# ARM_EURO_Platine2.net
KiCad netlist of a schematic drawn in Altium Designer
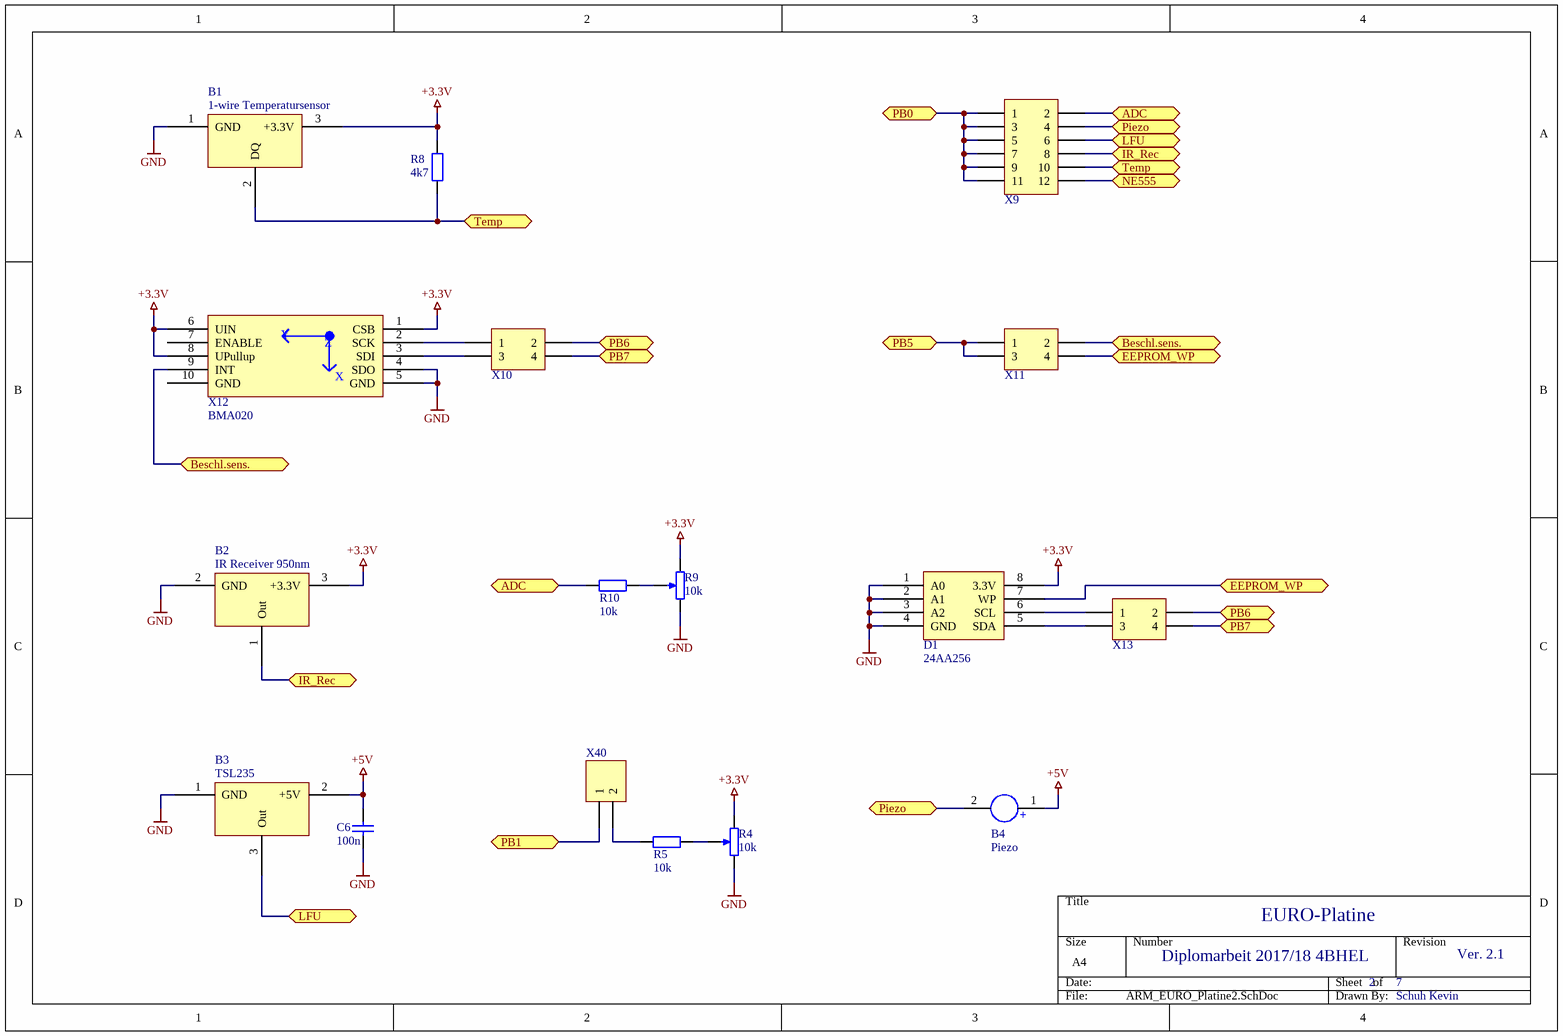
[diagram p0: ARM_EURO_Platine2.SchDoc]

(export (version "E")
  (design (tool "Eeschema 10.0.6"))
  (components
    (comp (ref "B1")
      (value "1-wire Temperatursensor")
      (footprint "TO_92")
      (description "Temperatursensor")
      (libsource (lib "ARM_Libary_EURO") (part "DS18B20"))
    )
    (comp (ref "B2")
      (value "IR Receiver 950nm")
      (footprint "TSOP341")
      (description "IR-Empfänger")
      (libsource (lib "ARM_Libary_EURO") (part "IR_Receiver"))
    )
    (comp (ref "B3")
      (value "TSL235")
      (footprint "LFU")
      (description "Licht/Frequenz - Umwandler")
      (libsource (lib "ARM_Libary_EURO") (part "LFU"))
    )
    (comp (ref "B4")
      (value "Piezo")
      (footprint "Piezo")
      (description "Signalgeber")
      (libsource (lib "ARM_Libary_EURO") (part "Piezo"))
    )
    (comp (ref "C6")
      (value "100n")
      (footprint "0805_CAP")
      (description "Capacitor_SMD")
      (fields (field (name "Comment") "Cap_Keramik_SMD") (field (name "PUBLISHER") "Altium Limited"))
      (libsource (lib "ARM_Libary_EURO") (part "Cap_Keramik_SMD"))
    )
    (comp (ref "D1")
      (value "24AA256")
      (footprint "PDIP8")
      (description "32kx8 EEPROM")
      (libsource (lib "ARM_Libary_EURO") (part "EEPROM"))
    )
    (comp (ref "R4")
      (value "10k")
      (footprint "Potentiometer")
      (description "Potentiometer")
      (fields (field (name "Comment") "RPot") (field (name "PUBLISHER") "Altium Limited"))
      (libsource (lib "ARM_Libary_EURO") (part "RPot"))
    )
    (comp (ref "R5")
      (value "10k")
      (footprint "0805_Res")
      (description "Resistor")
      (fields (field (name "Comment") "Res_SMD") (field (name "PUBLISHER") "Altium Limited"))
      (libsource (lib "ARM_Libary_EURO") (part "Res_SMD"))
    )
    (comp (ref "R8")
      (value "4k7")
      (footprint "0805_Res")
      (description "Resistor")
      (fields (field (name "Comment") "Res_SMD") (field (name "PUBLISHER") "Altium Limited"))
      (libsource (lib "") (part "Res_SMD_1"))
    )
    (comp (ref "R9")
      (value "10k")
      (footprint "Potentiometer")
      (description "Potentiometer")
      (fields (field (name "Comment") "RPot") (field (name "PUBLISHER") "Altium Limited"))
      (libsource (lib "ARM_Libary_EURO") (part "RPot"))
    )
    (comp (ref "R10")
      (value "10k")
      (footprint "0805_Res")
      (description "Resistor")
      (fields (field (name "Comment") "Res_SMD") (field (name "PUBLISHER") "Altium Limited"))
      (libsource (lib "ARM_Libary_EURO") (part "Res_SMD"))
    )
    (comp (ref "X9")
      (value "Header 6X2A")
      (footprint "HDR2X6")
      (description "Header, 6-Pin, Dual row")
      (fields (field (name "PUBLISHER") "Altium Limited"))
      (libsource (lib "ARM_Libary_EURO") (part "Header_6X2A"))
    )
    (comp (ref "X10")
      (value "Header_2x2")
      (footprint "HDR2X2")
      (description "Header, 3x2-Pin")
      (fields (field (name "PUBLISHER") "Altium Limited"))
      (libsource (lib "ARM_Libary_EURO") (part "Header_2x2"))
    )
    (comp (ref "X11")
      (value "Header_2x2")
      (footprint "HDR2X2")
      (description "Header, 3x2-Pin")
      (fields (field (name "PUBLISHER") "Altium Limited"))
      (libsource (lib "ARM_Libary_EURO") (part "Header_2x2"))
    )
    (comp (ref "X12")
      (value "BMA020")
      (footprint "Beschleunigungssensor")
      (description "3-Achsen Beschleunigungssensor-Modul")
      (libsource (lib "ARM_Libary_EURO") (part "Beschleunigungssensor"))
    )
    (comp (ref "X13")
      (value "Header_2x2")
      (footprint "HDR2X2")
      (description "Header, 3x2-Pin")
      (fields (field (name "PUBLISHER") "Altium Limited"))
      (libsource (lib "ARM_Libary_EURO") (part "Header_2x2"))
    )
    (comp (ref "X40")
      (value "Header")
      (footprint "HDR1X2")
      (description "Header, 2-Pin")
      (fields (field (name "PUBLISHER") "Altium Limited"))
      (libsource (lib "ARM_Libary_EURO") (part "Header_2"))
    )
  )
  (nets
    (net (code "1") (name "+3.3V") (class "Default")
      (node (ref "B1") (pin "3") (pinfunction "+3.3V_3") (pintype "passive"))
      (node (ref "B2") (pin "3") (pinfunction "+3.3V_3") (pintype "passive"))
      (node (ref "D1") (pin "8") (pinfunction "3.3V_8") (pintype "passive"))
      (node (ref "R4") (pin "1") (pinfunction "TOP_1") (pintype "passive"))
      (node (ref "R8") (pin "2") (pinfunction "2_2") (pintype "passive"))
      (node (ref "R9") (pin "1") (pinfunction "TOP_1") (pintype "passive"))
      (node (ref "X12") (pin "1") (pinfunction "CSB_1") (pintype "passive"))
      (node (ref "X12") (pin "6") (pinfunction "UIN_6") (pintype "passive"))
      (node (ref "X12") (pin "8") (pinfunction "UPullup_8") (pintype "passive"))
    )
    (net (code "2") (name "+5V") (class "Default")
      (node (ref "B3") (pin "2") (pinfunction "+5V_2") (pintype "passive"))
      (node (ref "B4") (pin "1") (pinfunction "1_1") (pintype "passive"))
      (node (ref "C6") (pin "2") (pinfunction "2_2") (pintype "passive"))
    )
    (net (code "3") (name "/ADC") (class "Default")
      (node (ref "R10") (pin "2") (pinfunction "2_2") (pintype "passive"))
      (node (ref "X9") (pin "2") (pinfunction "2_2") (pintype "passive"))
    )
    (net (code "4") (name "/Beschl.sens.") (class "Default")
      (node (ref "X11") (pin "2") (pinfunction "2_2") (pintype "passive"))
      (node (ref "X12") (pin "9") (pinfunction "INT_9") (pintype "passive"))
    )
    (net (code "5") (name "/EEPROM_WP") (class "Default")
      (node (ref "D1") (pin "7") (pinfunction "WP_7") (pintype "passive"))
      (node (ref "X11") (pin "4") (pinfunction "4_4") (pintype "passive"))
    )
    (net (code "6") (name "/IR_Rec") (class "Default")
      (node (ref "B2") (pin "1") (pinfunction "Out_1") (pintype "passive"))
      (node (ref "X9") (pin "8") (pinfunction "8_8") (pintype "passive"))
    )
    (net (code "7") (name "/LFU") (class "Default")
      (node (ref "B3") (pin "3") (pinfunction "Out_3") (pintype "passive"))
      (node (ref "X9") (pin "6") (pinfunction "6_6") (pintype "passive"))
    )
    (net (code "8") (name "/NE555") (class "Default")
      (node (ref "X9") (pin "12") (pinfunction "12_12") (pintype "passive"))
    )
    (net (code "9") (name "/PB0") (class "Default")
      (node (ref "X9") (pin "1") (pinfunction "1_1") (pintype "passive"))
      (node (ref "X9") (pin "11") (pinfunction "11_11") (pintype "passive"))
      (node (ref "X9") (pin "3") (pinfunction "3_3") (pintype "passive"))
      (node (ref "X9") (pin "5") (pinfunction "5_5") (pintype "passive"))
      (node (ref "X9") (pin "7") (pinfunction "7_7") (pintype "passive"))
      (node (ref "X9") (pin "9") (pinfunction "9_9") (pintype "passive"))
    )
    (net (code "10") (name "/PB1") (class "Default")
      (node (ref "X40") (pin "1") (pinfunction "1_1") (pintype "passive"))
    )
    (net (code "11") (name "/PB5") (class "Default")
      (node (ref "X11") (pin "1") (pinfunction "1_1") (pintype "passive"))
      (node (ref "X11") (pin "3") (pinfunction "3_3") (pintype "passive"))
    )
    (net (code "12") (name "/PB6") (class "Default")
      (node (ref "X10") (pin "2") (pinfunction "2_2") (pintype "passive"))
      (node (ref "X13") (pin "2") (pinfunction "2_2") (pintype "passive"))
    )
    (net (code "13") (name "/PB7") (class "Default")
      (node (ref "X10") (pin "4") (pinfunction "4_4") (pintype "passive"))
      (node (ref "X13") (pin "4") (pinfunction "4_4") (pintype "passive"))
    )
    (net (code "14") (name "/Piezo") (class "Default")
      (node (ref "B4") (pin "2") (pinfunction "2_2") (pintype "passive"))
      (node (ref "X9") (pin "4") (pinfunction "4_4") (pintype "passive"))
    )
    (net (code "15") (name "/Temp") (class "Default")
      (node (ref "B1") (pin "2") (pinfunction "DQ_2") (pintype "passive"))
      (node (ref "R8") (pin "1") (pinfunction "1_1") (pintype "passive"))
      (node (ref "X9") (pin "10") (pinfunction "10_10") (pintype "passive"))
    )
    (net (code "16") (name "GND") (class "Default")
      (node (ref "B1") (pin "1") (pinfunction "GND_1") (pintype "passive"))
      (node (ref "B2") (pin "2") (pinfunction "GND_2") (pintype "passive"))
      (node (ref "B3") (pin "1") (pinfunction "GND_1") (pintype "passive"))
      (node (ref "C6") (pin "1") (pinfunction "1_1") (pintype "passive"))
      (node (ref "D1") (pin "1") (pinfunction "A0_1") (pintype "passive"))
      (node (ref "D1") (pin "2") (pinfunction "A1_2") (pintype "passive"))
      (node (ref "D1") (pin "3") (pinfunction "A2_3") (pintype "passive"))
      (node (ref "D1") (pin "4") (pinfunction "GND_4") (pintype "passive"))
      (node (ref "R4") (pin "2") (pinfunction "BOT_2") (pintype "passive"))
      (node (ref "R9") (pin "2") (pinfunction "BOT_2") (pintype "passive"))
      (node (ref "X12") (pin "4") (pinfunction "SDO_4") (pintype "passive"))
      (node (ref "X12") (pin "5") (pinfunction "GND_5") (pintype "passive"))
    )
    (net (code "17") (name "Net-(D1-SCL)") (class "Default")
      (node (ref "D1") (pin "6") (pinfunction "SCL_6") (pintype "passive"))
      (node (ref "X13") (pin "1") (pinfunction "1_1") (pintype "passive"))
    )
    (net (code "18") (name "Net-(D1-SDA)") (class "Default")
      (node (ref "D1") (pin "5") (pinfunction "SDA_5") (pintype "passive"))
      (node (ref "X13") (pin "3") (pinfunction "3_3") (pintype "passive"))
    )
    (net (code "19") (name "Net-(R4-TAP)") (class "Default")
      (node (ref "R4") (pin "3") (pinfunction "TAP_3") (pintype "passive"))
      (node (ref "R5") (pin "1") (pinfunction "1_1") (pintype "passive"))
    )
    (net (code "20") (name "Net-(R5-Pad2)") (class "Default")
      (node (ref "R5") (pin "2") (pinfunction "2_2") (pintype "passive"))
      (node (ref "X40") (pin "2") (pinfunction "2_2") (pintype "passive"))
    )
    (net (code "21") (name "Net-(R9-TAP)") (class "Default")
      (node (ref "R10") (pin "1") (pinfunction "1_1") (pintype "passive"))
      (node (ref "R9") (pin "3") (pinfunction "TAP_3") (pintype "passive"))
    )
    (net (code "22") (name "Net-(X12-SCK)") (class "Default")
      (node (ref "X10") (pin "1") (pinfunction "1_1") (pintype "passive"))
      (node (ref "X12") (pin "2") (pinfunction "SCK_2") (pintype "passive"))
    )
    (net (code "23") (name "Net-(X12-SDI)") (class "Default")
      (node (ref "X10") (pin "3") (pinfunction "3_3") (pintype "passive"))
      (node (ref "X12") (pin "3") (pinfunction "SDI_3") (pintype "passive"))
    )
    (net (code "24") (name "unconnected-(X12-ENABLE-Pad7)") (class "Default")
      (node (ref "X12") (pin "7") (pinfunction "ENABLE_7") (pintype "passive"))
    )
    (net (code "25") (name "unconnected-(X12-GND-Pad10)") (class "Default")
      (node (ref "X12") (pin "10") (pinfunction "GND_10") (pintype "passive"))
    )
  )
)
